# POWER_BOARD.net
KiCad netlist of a schematic drawn in Altium Designer
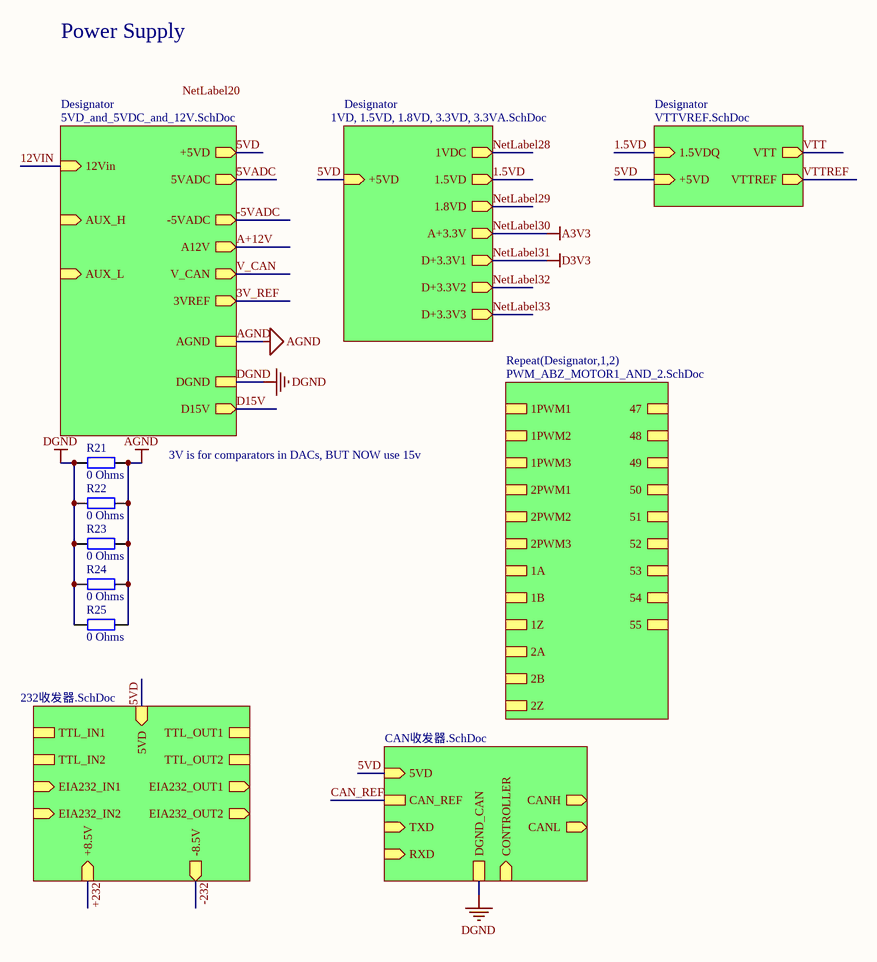
[diagram p0: POWER_BOARD.SchDoc]

(export (version "E")
  (design (tool "Eeschema 10.0.6"))
  (components
    (comp (ref "R21")
      (value "0 Ohms")
      (footprint "R 0805_L")
      (description "贴片电阻")
      (fields (field (name "版权归属") "来自淘宝 ID：黄晶宝石"))
      (libsource (lib "0.1 - 电阻-电容-电感") (part "R"))
    )
    (comp (ref "R22")
      (value "0 Ohms")
      (footprint "R 0805_L")
      (description "贴片电阻")
      (fields (field (name "版权归属") "来自淘宝 ID：黄晶宝石"))
      (libsource (lib "0.1 - 电阻-电容-电感") (part "R"))
    )
    (comp (ref "R23")
      (value "0 Ohms")
      (footprint "R 0805_L")
      (description "贴片电阻")
      (fields (field (name "版权归属") "来自淘宝 ID：黄晶宝石"))
      (libsource (lib "0.1 - 电阻-电容-电感") (part "R"))
    )
    (comp (ref "R24")
      (value "0 Ohms")
      (footprint "R 0805_L")
      (description "贴片电阻")
      (fields (field (name "版权归属") "来自淘宝 ID：黄晶宝石"))
      (libsource (lib "0.1 - 电阻-电容-电感") (part "R"))
    )
    (comp (ref "R25")
      (value "0 Ohms")
      (footprint "R 0805_L")
      (description "贴片电阻")
      (fields (field (name "版权归属") "来自淘宝 ID：黄晶宝石"))
      (libsource (lib "0.1 - 电阻-电容-电感") (part "R"))
    )
  )
  (nets
    (net (code "57") (name "AGND") (class "Default")
      (node (ref "R21") (pin "2") (pinfunction "2_2") (pintype "passive"))
      (node (ref "R22") (pin "2") (pinfunction "2_2") (pintype "passive"))
      (node (ref "R23") (pin "2") (pinfunction "2_2") (pintype "passive"))
      (node (ref "R24") (pin "2") (pinfunction "2_2") (pintype "passive"))
      (node (ref "R25") (pin "2") (pinfunction "2_2") (pintype "passive"))
    )
    (net (code "59") (name "DGND") (class "Default")
      (node (ref "R21") (pin "1") (pinfunction "1_1") (pintype "passive"))
      (node (ref "R22") (pin "1") (pinfunction "1_1") (pintype "passive"))
      (node (ref "R23") (pin "1") (pinfunction "1_1") (pintype "passive"))
      (node (ref "R24") (pin "1") (pinfunction "1_1") (pintype "passive"))
      (node (ref "R25") (pin "1") (pinfunction "1_1") (pintype "passive"))
    )
  )
)
